# screen_board.net
KiCad netlist of a schematic drawn in EAGLE
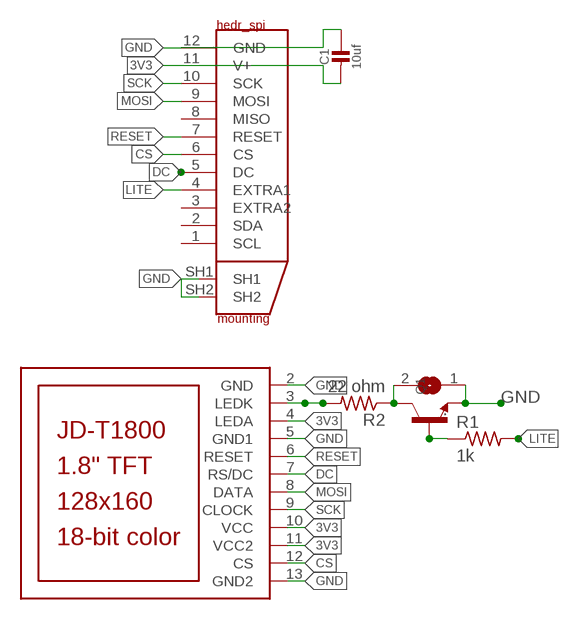
[diagram p0: schematic, sheet 1]

(export (version "E")
  (design (tool "Eeschema 10.0.6"))
  (components
    (comp (ref ".")
      (value "JUMPER_OPEN")
      (footprint "eagle-import:SOLDERJUMPER_ARROW_NOPASTE")
      (libsource (lib "eagle-import") (part "JUMPER_OPEN"))
    )
    (comp (ref "..")
      (value "HEDR-SPI-PFC_12SLAVE_EXTEN")
      (footprint "eagle-import:FPC_TE_1-1734839-2_EXTENDED")
      (libsource (lib "eagle-import") (part "HEDR-SPI-PFC_12SLAVE_EXTEN"))
    )
    (comp (ref "C1")
      (value "10uf")
      (footprint "eagle-import:MICROBUILDER_0805_NOTHERMALS")
      (libsource (lib "eagle-import") (part "C-US_0805-NOTHERMALS"))
    )
    (comp (ref "LCD2")
      (value "TFT-1.8-JD-T1800-_NO_DRILL_WRAP")
      (footprint "eagle-import:0TG-LIB-V01.1_JD-T1800-REV-WRAP_NO-DRILL")
      (libsource (lib "eagle-import") (part "TFT-1.8-JD-T1800-_NO_DRILL_WRAP"))
    )
    (comp (ref "Q1")
      (value "TRANSISTOR_NPNWIDE")
      (footprint "eagle-import:SOT23-WIDE")
      (libsource (lib "eagle-import") (part "TRANSISTOR_NPNWIDE"))
    )
    (comp (ref "R1")
      (value "1k")
      (footprint "eagle-import:R0805")
      (libsource (lib "eagle-import") (part "R-US_R0805"))
    )
    (comp (ref "R2")
      (value "22 ohm")
      (footprint "eagle-import:R0805")
      (libsource (lib "eagle-import") (part "R-US_R0805"))
    )
  )
  (nets
    (net (code "1") (name "3V3") (class "Default")
      (node (ref "..") (pin "11") (pinfunction "V+_11") (pintype "bidirectional"))
      (node (ref "C1") (pin "2") (pinfunction "2_2") (pintype "passive"))
      (node (ref "LCD2") (pin "10") (pinfunction "VCC_10") (pintype "power_in"))
      (node (ref "LCD2") (pin "11") (pinfunction "VCC2_11") (pintype "power_in"))
      (node (ref "LCD2") (pin "4") (pinfunction "LEDA_4") (pintype "input"))
    )
    (net (code "2") (name "CS") (class "Default")
      (node (ref "..") (pin "6") (pinfunction "CS_6") (pintype "bidirectional"))
      (node (ref "LCD2") (pin "12") (pinfunction "CS_12") (pintype "input"))
    )
    (net (code "3") (name "DC") (class "Default")
      (node (ref "..") (pin "5") (pinfunction "DC_5") (pintype "bidirectional"))
      (node (ref "LCD2") (pin "7") (pinfunction "RS/DC_7") (pintype "input"))
    )
    (net (code "4") (name "GND") (class "Default")
      (node (ref ".") (pin "1") (pinfunction "1_1") (pintype "passive"))
      (node (ref "..") (pin "12") (pinfunction "GND_12") (pintype "bidirectional"))
      (node (ref "..") (pin "SH1") (pinfunction "SH1_SH1") (pintype "bidirectional"))
      (node (ref "..") (pin "SH2") (pinfunction "SH2_SH2") (pintype "bidirectional"))
      (node (ref "C1") (pin "1") (pinfunction "1_1") (pintype "passive"))
      (node (ref "LCD2") (pin "13") (pinfunction "GND2_13") (pintype "power_in"))
      (node (ref "LCD2") (pin "2") (pinfunction "GND_2") (pintype "power_in"))
      (node (ref "LCD2") (pin "5") (pinfunction "GND1_5") (pintype "power_in"))
      (node (ref "Q1") (pin "2") (pinfunction "E_2") (pintype "passive"))
    )
    (net (code "5") (name "LITE") (class "Default")
      (node (ref "..") (pin "4") (pinfunction "EXTRA1_4") (pintype "bidirectional"))
      (node (ref "R1") (pin "2") (pinfunction "2_2") (pintype "passive"))
    )
    (net (code "6") (name "MOSI") (class "Default")
      (node (ref "..") (pin "9") (pinfunction "MOSI_9") (pintype "bidirectional"))
      (node (ref "LCD2") (pin "8") (pinfunction "DATA_8") (pintype "bidirectional"))
    )
    (net (code "7") (name "Net-(LCD2-LEDK)") (class "Default")
      (node (ref "LCD2") (pin "3") (pinfunction "LEDK_3") (pintype "input"))
      (node (ref "R2") (pin "2") (pinfunction "2_2") (pintype "passive"))
    )
    (net (code "8") (name "Net-(Q1-B)") (class "Default")
      (node (ref "Q1") (pin "1") (pinfunction "B_1") (pintype "passive"))
      (node (ref "R1") (pin "1") (pinfunction "1_1") (pintype "passive"))
    )
    (net (code "9") (name "Net-(Q1-C)") (class "Default")
      (node (ref ".") (pin "2") (pinfunction "2_2") (pintype "passive"))
      (node (ref "Q1") (pin "3") (pinfunction "C_3") (pintype "passive"))
      (node (ref "R2") (pin "1") (pinfunction "1_1") (pintype "passive"))
    )
    (net (code "10") (name "RESET") (class "Default")
      (node (ref "..") (pin "7") (pinfunction "RESET_7") (pintype "bidirectional"))
      (node (ref "LCD2") (pin "6") (pinfunction "RESET_6") (pintype "input"))
    )
    (net (code "11") (name "SCK") (class "Default")
      (node (ref "..") (pin "10") (pinfunction "SCK_10") (pintype "bidirectional"))
      (node (ref "LCD2") (pin "9") (pinfunction "CLOCK_9") (pintype "input"))
    )
    (net (code "12") (name "unconnected-(..-EXTRA2-Pad3)") (class "Default")
      (node (ref "..") (pin "3") (pinfunction "EXTRA2_3") (pintype "bidirectional"))
    )
    (net (code "13") (name "unconnected-(..-MISO-Pad8)") (class "Default")
      (node (ref "..") (pin "8") (pinfunction "MISO_8") (pintype "bidirectional"))
    )
    (net (code "14") (name "unconnected-(..-SCL-Pad1)") (class "Default")
      (node (ref "..") (pin "1") (pinfunction "SCL_1") (pintype "bidirectional"))
    )
    (net (code "15") (name "unconnected-(..-SDA-Pad2)") (class "Default")
      (node (ref "..") (pin "2") (pinfunction "SDA_2") (pintype "bidirectional"))
    )
  )
)
